# Pure_Digit.net
KiCad netlist of a schematic drawn in EAGLE
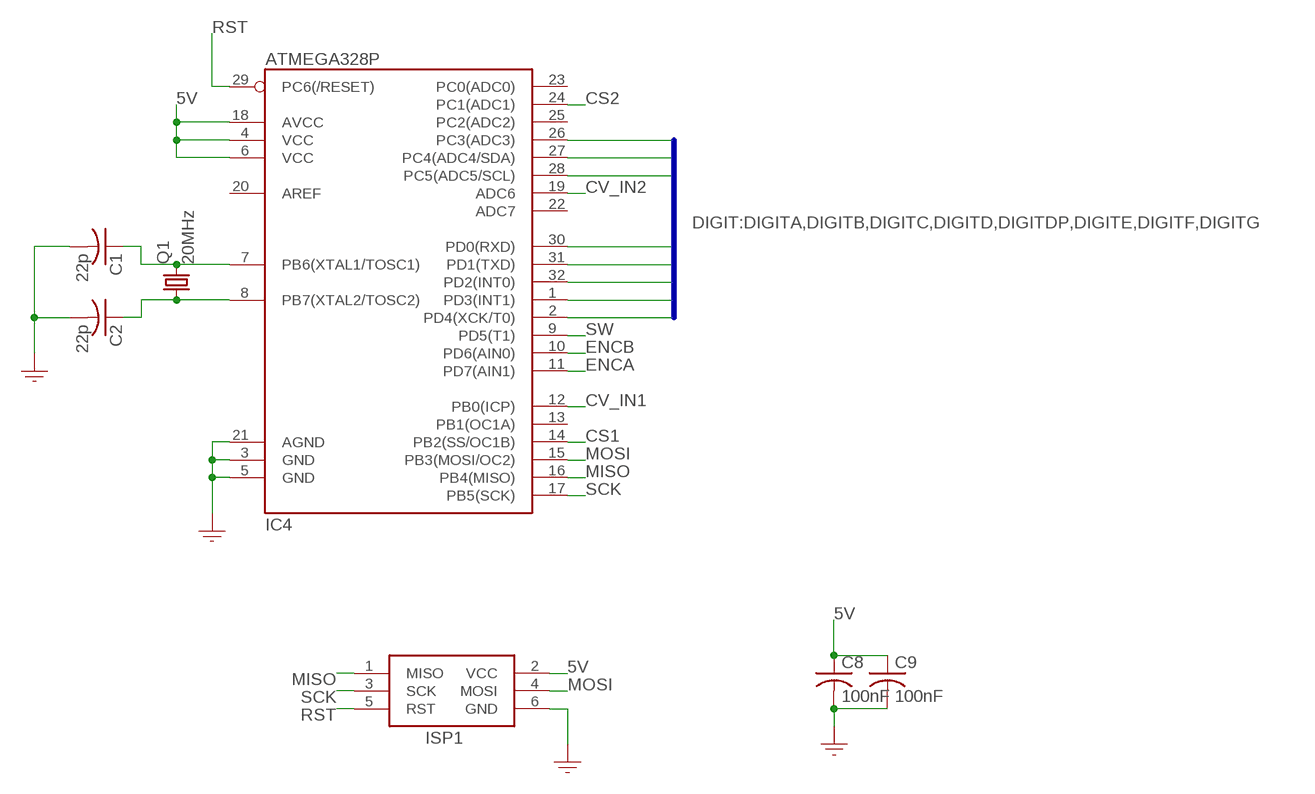
[diagram p0: schematic, sheet 1]
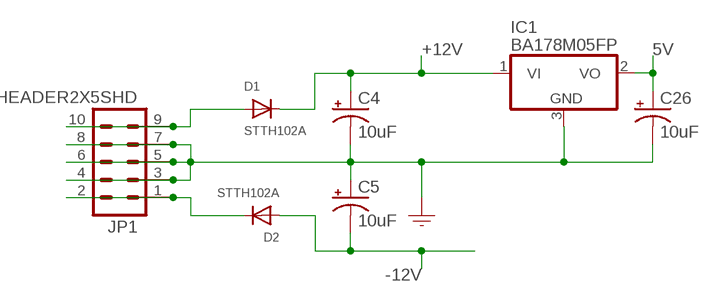
[diagram p1: schematic, sheet 2]
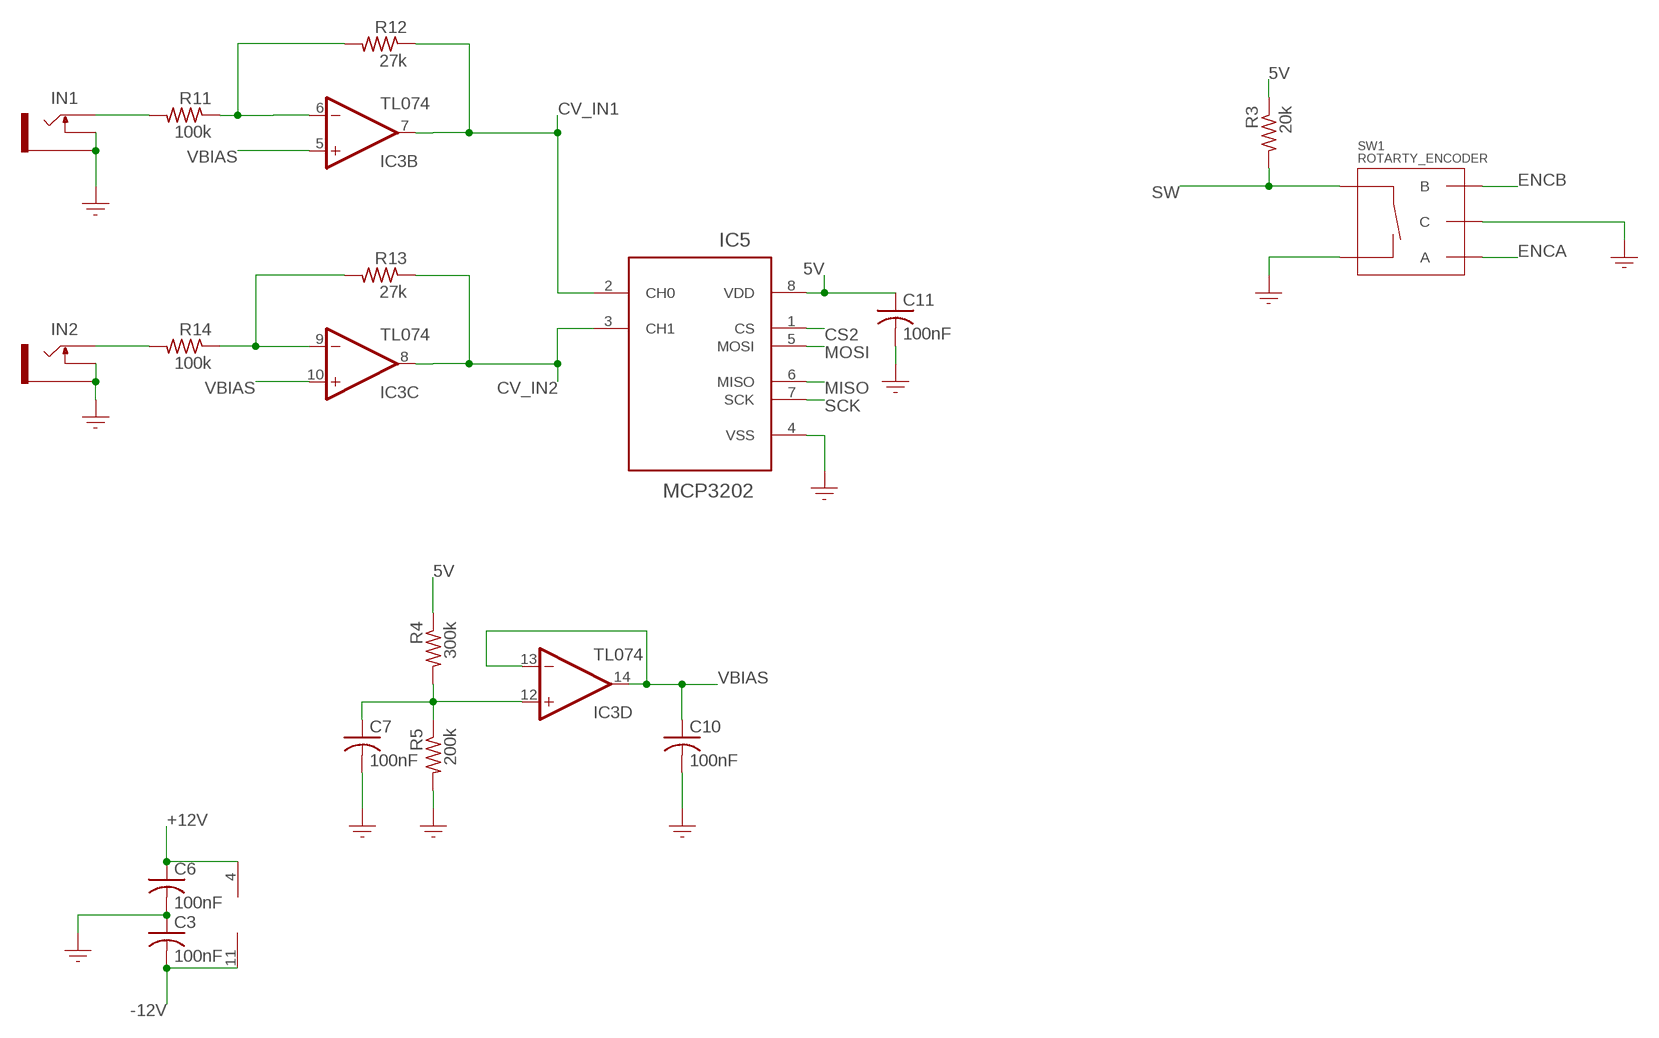
[diagram p2: schematic, sheet 3]
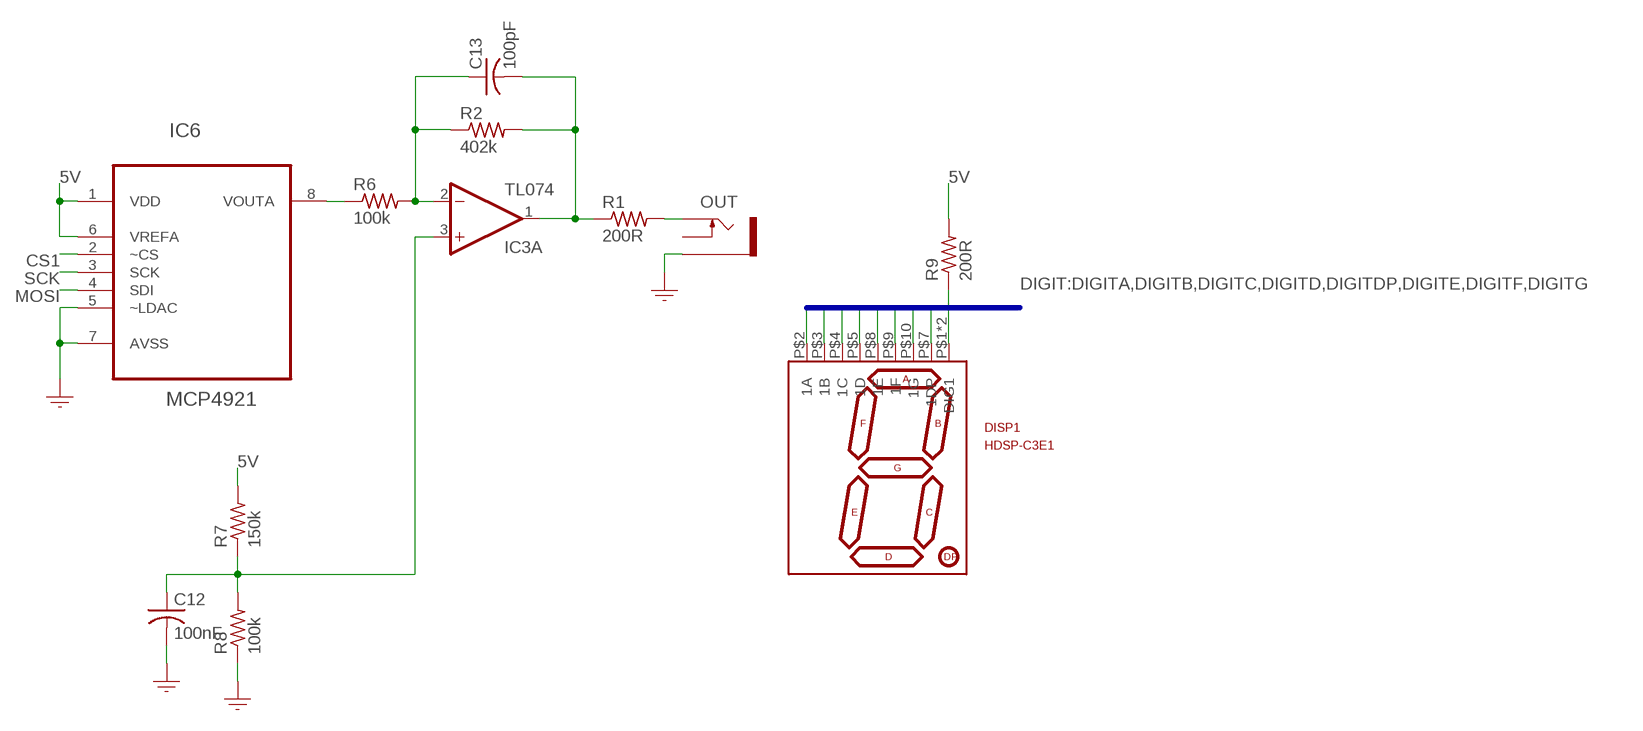
[diagram p3: schematic, sheet 4]

(export (version "E")
  (design (tool "Eeschema 10.0.6"))
  (components
    (comp (ref "C3")
      (value "100nF")
      (footprint "eagle-import:C0805")
      (libsource (lib "eagle-import") (part "CAPACITOR-USC0805"))
    )
    (comp (ref "C6")
      (value "100nF")
      (footprint "eagle-import:C0805")
      (libsource (lib "eagle-import") (part "CAPACITOR-USC0805"))
    )
    (comp (ref "C7")
      (value "100nF")
      (footprint "eagle-import:C0805")
      (libsource (lib "eagle-import") (part "CAPACITOR-USC0805"))
    )
    (comp (ref "C10")
      (value "100nF")
      (footprint "eagle-import:C0805")
      (libsource (lib "eagle-import") (part "CAPACITOR-USC0805"))
    )
    (comp (ref "C11")
      (value "100nF")
      (footprint "eagle-import:C0805")
      (libsource (lib "eagle-import") (part "CAPACITOR-USC0805"))
    )
    (comp (ref "IC3")
      (value "TL074")
      (footprint "eagle-import:SO14")
      (libsource (lib "eagle-import") (part "OPAMP_QUADD"))
    )
    (comp (ref "IC5")
      (value "MCP3202")
      (footprint "eagle-import:SOIC--8")
      (libsource (lib "eagle-import") (part "ADC_DUAL_12B_MCP3202"))
    )
    (comp (ref "IN1")
      (value "PJ301M-12")
      (footprint "eagle-import:PJ301M-12")
      (libsource (lib "eagle-import") (part "SOCKET_MONO_3.5MMPJ301M-12"))
    )
    (comp (ref "IN2")
      (value "PJ301M-12")
      (footprint "eagle-import:PJ301M-12")
      (libsource (lib "eagle-import") (part "SOCKET_MONO_3.5MMPJ301M-12"))
    )
    (comp (ref "R3")
      (value "20k")
      (footprint "eagle-import:R0805")
      (libsource (lib "eagle-import") (part "RESISTOR_USR0805"))
    )
    (comp (ref "R4")
      (value "300k")
      (footprint "eagle-import:R0805")
      (libsource (lib "eagle-import") (part "RESISTOR_USR0805"))
    )
    (comp (ref "R5")
      (value "200k")
      (footprint "eagle-import:R0805")
      (libsource (lib "eagle-import") (part "RESISTOR_USR0805"))
    )
    (comp (ref "R11")
      (value "100k")
      (footprint "eagle-import:R0805")
      (libsource (lib "eagle-import") (part "RESISTOR_USR0805"))
    )
    (comp (ref "R12")
      (value "27k")
      (footprint "eagle-import:R0805")
      (libsource (lib "eagle-import") (part "RESISTOR_USR0805"))
    )
    (comp (ref "R13")
      (value "27k")
      (footprint "eagle-import:R0805")
      (libsource (lib "eagle-import") (part "RESISTOR_USR0805"))
    )
    (comp (ref "R14")
      (value "100k")
      (footprint "eagle-import:R0805")
      (libsource (lib "eagle-import") (part "RESISTOR_USR0805"))
    )
    (comp (ref "SW1")
      (value "ROTARTY_ENCODER")
      (footprint "eagle-import:ROTARY_ENC_PLAIN")
      (libsource (lib "eagle-import") (part "ROTARTY_ENCODER"))
    )
    (comp (ref "C1")
      (value "22p")
      (footprint "eagle-import:C0805")
      (libsource (lib "eagle-import") (part "CAPACITOR-USC0805"))
    )
    (comp (ref "C2")
      (value "22p")
      (footprint "eagle-import:C0805")
      (libsource (lib "eagle-import") (part "CAPACITOR-USC0805"))
    )
    (comp (ref "C8")
      (value "100nF")
      (footprint "eagle-import:C0805")
      (libsource (lib "eagle-import") (part "CAPACITOR-USC0805"))
    )
    (comp (ref "C9")
      (value "100nF")
      (footprint "eagle-import:C0805")
      (libsource (lib "eagle-import") (part "CAPACITOR-USC0805"))
    )
    (comp (ref "IC4")
      (value "ATMEGA328P")
      (footprint "eagle-import:TQFP32-08")
      (libsource (lib "eagle-import") (part "MICROPROCESSOR_ATMEGA328_SMT"))
    )
    (comp (ref "ISP1")
      (value "HEADER2X3-6")
      (footprint "eagle-import:AVRISP")
      (libsource (lib "eagle-import") (part "HEADER2X3-6"))
    )
    (comp (ref "Q1")
      (value "20MHz")
      (footprint "eagle-import:SM49")
      (libsource (lib "eagle-import") (part "CRYSTALSM49"))
    )
    (comp (ref "C12")
      (value "100nF")
      (footprint "eagle-import:C0805")
      (libsource (lib "eagle-import") (part "CAPACITOR-USC0805"))
    )
    (comp (ref "C13")
      (value "100pF")
      (footprint "eagle-import:C0805")
      (libsource (lib "eagle-import") (part "CAPACITOR-USC0805"))
    )
    (comp (ref "DISP1")
      (value "HDSP-C3E1")
      (footprint "eagle-import:7-SEGMENT-1DIGIT")
      (libsource (lib "eagle-import") (part "DISPLAY_7-SEGMENT-1DIGIT"))
    )
    (comp (ref "IC6")
      (value "MCP4921")
      (footprint "eagle-import:SOIC8")
      (libsource (lib "eagle-import") (part "DAC_SINGLE_12B_MCP4921"))
    )
    (comp (ref "OUT")
      (value "PJ301M-12")
      (footprint "eagle-import:PJ301M-12")
      (libsource (lib "eagle-import") (part "SOCKET_MONO_3.5MMPJ301M-12"))
    )
    (comp (ref "R1")
      (value "200R")
      (footprint "eagle-import:R0805")
      (libsource (lib "eagle-import") (part "RESISTOR_USR0805"))
    )
    (comp (ref "R2")
      (value "402k")
      (footprint "eagle-import:R0805")
      (libsource (lib "eagle-import") (part "RESISTOR_USR0805"))
    )
    (comp (ref "R6")
      (value "100k")
      (footprint "eagle-import:R0805")
      (libsource (lib "eagle-import") (part "RESISTOR_USR0805"))
    )
    (comp (ref "R7")
      (value "150k")
      (footprint "eagle-import:R0805")
      (libsource (lib "eagle-import") (part "RESISTOR_USR0805"))
    )
    (comp (ref "R8")
      (value "100k")
      (footprint "eagle-import:R0805")
      (libsource (lib "eagle-import") (part "RESISTOR_USR0805"))
    )
    (comp (ref "R9")
      (value "200R")
      (footprint "eagle-import:R0805")
      (libsource (lib "eagle-import") (part "RESISTOR_USR0805"))
    )
    (comp (ref "C4")
      (value "10uF")
      (footprint "eagle-import:153CLV-0505")
      (libsource (lib "eagle-import") (part "CAPACITOR_POL-US153CLV-0505"))
    )
    (comp (ref "C5")
      (value "10uF")
      (footprint "eagle-import:153CLV-0505")
      (libsource (lib "eagle-import") (part "CAPACITOR_POL-US153CLV-0505"))
    )
    (comp (ref "C26")
      (value "10uF")
      (footprint "eagle-import:153CLV-0505")
      (libsource (lib "eagle-import") (part "CAPACITOR_POL-US153CLV-0505"))
    )
    (comp (ref "D1")
      (value "STTH102A")
      (footprint "eagle-import:SMADIODE")
      (libsource (lib "eagle-import") (part "DIODESMA"))
    )
    (comp (ref "D2")
      (value "STTH102A")
      (footprint "eagle-import:SMADIODE")
      (libsource (lib "eagle-import") (part "DIODESMA"))
    )
    (comp (ref "IC1")
      (value "BA178M05FP")
      (footprint "eagle-import:TO252")
      (libsource (lib "eagle-import") (part "VOLTAGE_REG_POSDT05"))
    )
    (comp (ref "JP1")
      (value "HEADER2X5SHD")
      (footprint "eagle-import:2X5-SHROUDED")
      (libsource (lib "eagle-import") (part "HEADER2X5SHD"))
    )
  )
  (nets
    (net (code "3") (name "+12V") (class "Default")
      (node (ref "C4") (pin "+") (pinfunction "+_+") (pintype "passive"))
      (node (ref "C6") (pin "1") (pinfunction "1_1") (pintype "passive"))
      (node (ref "D1") (pin "C") (pinfunction "C_C") (pintype "passive"))
      (node (ref "IC1") (pin "1") (pinfunction "VI_1") (pintype "input"))
      (node (ref "IC3") (pin "4") (pinfunction "V+_4") (pintype "power_in"))
    )
    (net (code "4") (name "-12V") (class "Default")
      (node (ref "C3") (pin "2") (pinfunction "2_2") (pintype "passive"))
      (node (ref "C5") (pin "-") (pinfunction "-_-") (pintype "passive"))
      (node (ref "D2") (pin "A") (pinfunction "A_A") (pintype "passive"))
      (node (ref "IC3") (pin "11") (pinfunction "V-_11") (pintype "power_in"))
    )
    (net (code "7") (name "5V") (class "Default")
      (node (ref "C11") (pin "1") (pinfunction "1_1") (pintype "passive"))
      (node (ref "C26") (pin "+") (pinfunction "+_+") (pintype "passive"))
      (node (ref "C8") (pin "1") (pinfunction "1_1") (pintype "passive"))
      (node (ref "C9") (pin "1") (pinfunction "1_1") (pintype "passive"))
      (node (ref "IC1") (pin "2") (pinfunction "VO_2") (pintype "passive"))
      (node (ref "IC4") (pin "18") (pinfunction "AVCC_18") (pintype "bidirectional"))
      (node (ref "IC4") (pin "4") (pinfunction "VCC_4") (pintype "bidirectional"))
      (node (ref "IC4") (pin "6") (pinfunction "VCC_6") (pintype "bidirectional"))
      (node (ref "IC5") (pin "8") (pinfunction "VDD_8") (pintype "bidirectional"))
      (node (ref "IC6") (pin "1") (pinfunction "VDD_1") (pintype "power_in"))
      (node (ref "IC6") (pin "6") (pinfunction "VREFA_6") (pintype "input"))
      (node (ref "ISP1") (pin "2") (pinfunction "VCC_2") (pintype "power_in"))
      (node (ref "R3") (pin "1") (pinfunction "1_1") (pintype "passive"))
      (node (ref "R4") (pin "1") (pinfunction "1_1") (pintype "passive"))
      (node (ref "R7") (pin "2") (pinfunction "2_2") (pintype "passive"))
      (node (ref "R9") (pin "2") (pinfunction "2_2") (pintype "passive"))
    )
    (net (code "8") (name "CS1") (class "Default")
      (node (ref "IC4") (pin "14") (pinfunction "PB2(SS/OC1B)_14") (pintype "bidirectional"))
      (node (ref "IC6") (pin "2") (pinfunction "~{CS}_2") (pintype "input"))
    )
    (net (code "9") (name "CS2") (class "Default")
      (node (ref "IC4") (pin "24") (pinfunction "PC1(ADC1)_24") (pintype "bidirectional"))
      (node (ref "IC5") (pin "1") (pinfunction "CS_1") (pintype "bidirectional"))
    )
    (net (code "10") (name "CV_IN1") (class "Default")
      (node (ref "IC3") (pin "7") (pinfunction "OUT_7") (pintype "output"))
      (node (ref "IC4") (pin "12") (pinfunction "PB0(ICP)_12") (pintype "bidirectional"))
      (node (ref "IC5") (pin "2") (pinfunction "CH0_2") (pintype "bidirectional"))
      (node (ref "R12") (pin "1") (pinfunction "1_1") (pintype "passive"))
    )
    (net (code "11") (name "CV_IN2") (class "Default")
      (node (ref "IC3") (pin "8") (pinfunction "OUT_8") (pintype "output"))
      (node (ref "IC4") (pin "19") (pinfunction "ADC6_19") (pintype "bidirectional"))
      (node (ref "IC5") (pin "3") (pinfunction "CH1_3") (pintype "bidirectional"))
      (node (ref "R13") (pin "1") (pinfunction "1_1") (pintype "passive"))
    )
    (net (code "12") (name "DIGITA") (class "Default")
      (node (ref "DISP1") (pin "P$2") (pinfunction "1A_P$2") (pintype "bidirectional"))
      (node (ref "IC4") (pin "30") (pinfunction "PD0(RXD)_30") (pintype "bidirectional"))
    )
    (net (code "13") (name "DIGITB") (class "Default")
      (node (ref "DISP1") (pin "P$3") (pinfunction "1B_P$3") (pintype "bidirectional"))
      (node (ref "IC4") (pin "28") (pinfunction "PC5(ADC5/SCL)_28") (pintype "bidirectional"))
    )
    (net (code "14") (name "DIGITC") (class "Default")
      (node (ref "DISP1") (pin "P$4") (pinfunction "1C_P$4") (pintype "bidirectional"))
      (node (ref "IC4") (pin "27") (pinfunction "PC4(ADC4/SDA)_27") (pintype "bidirectional"))
    )
    (net (code "15") (name "DIGITD") (class "Default")
      (node (ref "DISP1") (pin "P$5") (pinfunction "1D_P$5") (pintype "bidirectional"))
      (node (ref "IC4") (pin "26") (pinfunction "PC3(ADC3)_26") (pintype "bidirectional"))
    )
    (net (code "16") (name "DIGITDP") (class "Default")
      (node (ref "DISP1") (pin "P$7") (pinfunction "1DP_P$7") (pintype "bidirectional"))
      (node (ref "IC4") (pin "1") (pinfunction "PD3(INT1)_1") (pintype "bidirectional"))
    )
    (net (code "17") (name "DIGITE") (class "Default")
      (node (ref "DISP1") (pin "P$8") (pinfunction "1E_P$8") (pintype "bidirectional"))
      (node (ref "IC4") (pin "2") (pinfunction "PD4(XCK/T0)_2") (pintype "bidirectional"))
    )
    (net (code "18") (name "DIGITF") (class "Default")
      (node (ref "DISP1") (pin "P$9") (pinfunction "1F_P$9") (pintype "bidirectional"))
      (node (ref "IC4") (pin "32") (pinfunction "PD2(INT0)_32") (pintype "bidirectional"))
    )
    (net (code "19") (name "DIGITG") (class "Default")
      (node (ref "DISP1") (pin "P$10") (pinfunction "1G_P$10") (pintype "bidirectional"))
      (node (ref "IC4") (pin "31") (pinfunction "PD1(TXD)_31") (pintype "bidirectional"))
    )
    (net (code "20") (name "ENCA") (class "Default")
      (node (ref "IC4") (pin "11") (pinfunction "PD7(AIN1)_11") (pintype "bidirectional"))
      (node (ref "SW1") (pin "A") (pinfunction "A_A") (pintype "bidirectional"))
    )
    (net (code "21") (name "ENCB") (class "Default")
      (node (ref "IC4") (pin "10") (pinfunction "PD6(AIN0)_10") (pintype "bidirectional"))
      (node (ref "SW1") (pin "B") (pinfunction "B_B") (pintype "bidirectional"))
    )
    (net (code "22") (name "GND") (class "Default")
      (node (ref "C1") (pin "2") (pinfunction "2_2") (pintype "passive"))
      (node (ref "C10") (pin "2") (pinfunction "2_2") (pintype "passive"))
      (node (ref "C11") (pin "2") (pinfunction "2_2") (pintype "passive"))
      (node (ref "C12") (pin "2") (pinfunction "2_2") (pintype "passive"))
      (node (ref "C2") (pin "2") (pinfunction "2_2") (pintype "passive"))
      (node (ref "C26") (pin "-") (pinfunction "-_-") (pintype "passive"))
      (node (ref "C3") (pin "1") (pinfunction "1_1") (pintype "passive"))
      (node (ref "C4") (pin "-") (pinfunction "-_-") (pintype "passive"))
      (node (ref "C5") (pin "+") (pinfunction "+_+") (pintype "passive"))
      (node (ref "C6") (pin "2") (pinfunction "2_2") (pintype "passive"))
      (node (ref "C7") (pin "2") (pinfunction "2_2") (pintype "passive"))
      (node (ref "C8") (pin "2") (pinfunction "2_2") (pintype "passive"))
      (node (ref "C9") (pin "2") (pinfunction "2_2") (pintype "passive"))
      (node (ref "IC1") (pin "3") (pinfunction "GND_3") (pintype "passive"))
      (node (ref "IC4") (pin "21") (pinfunction "AGND_21") (pintype "bidirectional"))
      (node (ref "IC4") (pin "3") (pinfunction "GND_3") (pintype "bidirectional"))
      (node (ref "IC4") (pin "5") (pinfunction "GND_5") (pintype "bidirectional"))
      (node (ref "IC5") (pin "4") (pinfunction "VSS_4") (pintype "bidirectional"))
      (node (ref "IC6") (pin "5") (pinfunction "~{LDAC}_5") (pintype "input"))
      (node (ref "IC6") (pin "7") (pinfunction "AVSS_7") (pintype "passive"))
      (node (ref "IN1") (pin "GND") (pinfunction "SLEEVE_GND") (pintype "passive"))
      (node (ref "IN1") (pin "NORM") (pinfunction "SWITCH_NORM") (pintype "passive"))
      (node (ref "IN2") (pin "GND") (pinfunction "SLEEVE_GND") (pintype "passive"))
      (node (ref "IN2") (pin "NORM") (pinfunction "SWITCH_NORM") (pintype "passive"))
      (node (ref "ISP1") (pin "6") (pinfunction "GND_6") (pintype "power_in"))
      (node (ref "JP1") (pin "3") (pinfunction "3_3") (pintype "passive"))
      (node (ref "JP1") (pin "4") (pinfunction "4_4") (pintype "passive"))
      (node (ref "JP1") (pin "5") (pinfunction "5_5") (pintype "passive"))
      (node (ref "JP1") (pin "6") (pinfunction "6_6") (pintype "passive"))
      (node (ref "JP1") (pin "7") (pinfunction "7_7") (pintype "passive"))
      (node (ref "JP1") (pin "8") (pinfunction "8_8") (pintype "passive"))
      (node (ref "OUT") (pin "GND") (pinfunction "SLEEVE_GND") (pintype "passive"))
      (node (ref "R5") (pin "2") (pinfunction "2_2") (pintype "passive"))
      (node (ref "R8") (pin "1") (pinfunction "1_1") (pintype "passive"))
      (node (ref "SW1") (pin "C") (pinfunction "C_C") (pintype "bidirectional"))
      (node (ref "SW1") (pin "SW-") (pinfunction "SW-_SW-") (pintype "bidirectional"))
    )
    (net (code "23") (name "MISO") (class "Default")
      (node (ref "IC4") (pin "16") (pinfunction "PB4(MISO)_16") (pintype "bidirectional"))
      (node (ref "IC5") (pin "6") (pinfunction "MISO_6") (pintype "bidirectional"))
      (node (ref "ISP1") (pin "1") (pinfunction "MISO_1") (pintype "input"))
    )
    (net (code "24") (name "MOSI") (class "Default")
      (node (ref "IC4") (pin "15") (pinfunction "PB3(MOSI/OC2)_15") (pintype "bidirectional"))
      (node (ref "IC5") (pin "5") (pinfunction "MOSI_5") (pintype "bidirectional"))
      (node (ref "IC6") (pin "4") (pinfunction "SDI_4") (pintype "input"))
      (node (ref "ISP1") (pin "4") (pinfunction "MOSI_4") (pintype "output"))
    )
    (net (code "25") (name "Net-(D1-PadA)") (class "Default")
      (node (ref "D1") (pin "A") (pinfunction "A_A") (pintype "passive"))
      (node (ref "JP1") (pin "10") (pinfunction "10_10") (pintype "passive"))
      (node (ref "JP1") (pin "9") (pinfunction "9_9") (pintype "passive"))
    )
    (net (code "26") (name "Net-(D2-PadC)") (class "Default")
      (node (ref "D2") (pin "C") (pinfunction "C_C") (pintype "passive"))
      (node (ref "JP1") (pin "1") (pinfunction "1_1") (pintype "passive"))
      (node (ref "JP1") (pin "2") (pinfunction "2_2") (pintype "passive"))
    )
    (net (code "27") (name "Net-(DISP1-DIG1-PadP$1)") (class "Default")
      (node (ref "DISP1") (pin "P$1") (pinfunction "DIG1_P$1") (pintype "bidirectional"))
      (node (ref "DISP1") (pin "P$6") (pinfunction "DIG1_P$6") (pintype "bidirectional"))
      (node (ref "R9") (pin "1") (pinfunction "1_1") (pintype "passive"))
    )
    (net (code "28") (name "Net-(IC3A-+IN)") (class "Default")
      (node (ref "C12") (pin "1") (pinfunction "1_1") (pintype "passive"))
      (node (ref "IC3") (pin "3") (pinfunction "+IN_3") (pintype "input"))
      (node (ref "R7") (pin "1") (pinfunction "1_1") (pintype "passive"))
      (node (ref "R8") (pin "2") (pinfunction "2_2") (pintype "passive"))
    )
    (net (code "29") (name "Net-(IC3A--IN)") (class "Default")
      (node (ref "C13") (pin "1") (pinfunction "1_1") (pintype "passive"))
      (node (ref "IC3") (pin "2") (pinfunction "-IN_2") (pintype "input"))
      (node (ref "R2") (pin "1") (pinfunction "1_1") (pintype "passive"))
      (node (ref "R6") (pin "2") (pinfunction "2_2") (pintype "passive"))
    )
    (net (code "30") (name "Net-(IC3A-OUT)") (class "Default")
      (node (ref "C13") (pin "2") (pinfunction "2_2") (pintype "passive"))
      (node (ref "IC3") (pin "1") (pinfunction "OUT_1") (pintype "output"))
      (node (ref "R1") (pin "1") (pinfunction "1_1") (pintype "passive"))
      (node (ref "R2") (pin "2") (pinfunction "2_2") (pintype "passive"))
    )
    (net (code "31") (name "Net-(IC3B--IN)") (class "Default")
      (node (ref "IC3") (pin "6") (pinfunction "-IN_6") (pintype "input"))
      (node (ref "R11") (pin "1") (pinfunction "1_1") (pintype "passive"))
      (node (ref "R12") (pin "2") (pinfunction "2_2") (pintype "passive"))
    )
    (net (code "32") (name "Net-(IC3C--IN)") (class "Default")
      (node (ref "IC3") (pin "9") (pinfunction "-IN_9") (pintype "input"))
      (node (ref "R13") (pin "2") (pinfunction "2_2") (pintype "passive"))
      (node (ref "R14") (pin "1") (pinfunction "1_1") (pintype "passive"))
    )
    (net (code "33") (name "Net-(IC3D-+IN)") (class "Default")
      (node (ref "C7") (pin "1") (pinfunction "1_1") (pintype "passive"))
      (node (ref "IC3") (pin "12") (pinfunction "+IN_12") (pintype "input"))
      (node (ref "R4") (pin "2") (pinfunction "2_2") (pintype "passive"))
      (node (ref "R5") (pin "1") (pinfunction "1_1") (pintype "passive"))
    )
    (net (code "34") (name "Net-(IC4-PB6(XTAL1{slash}TOSC1))") (class "Default")
      (node (ref "C1") (pin "1") (pinfunction "1_1") (pintype "passive"))
      (node (ref "IC4") (pin "7") (pinfunction "PB6(XTAL1/TOSC1)_7") (pintype "bidirectional"))
      (node (ref "Q1") (pin "2") (pinfunction "2_2") (pintype "passive"))
    )
    (net (code "35") (name "Net-(IC4-PB7(XTAL2{slash}TOSC2))") (class "Default")
      (node (ref "C2") (pin "1") (pinfunction "1_1") (pintype "passive"))
      (node (ref "IC4") (pin "8") (pinfunction "PB7(XTAL2/TOSC2)_8") (pintype "bidirectional"))
      (node (ref "Q1") (pin "1") (pinfunction "1_1") (pintype "passive"))
    )
    (net (code "36") (name "Net-(IC6-VOUTA)") (class "Default")
      (node (ref "IC6") (pin "8") (pinfunction "VOUTA_8") (pintype "output"))
      (node (ref "R6") (pin "1") (pinfunction "1_1") (pintype "passive"))
    )
    (net (code "37") (name "Net-(IN1-PadTIP)") (class "Default")
      (node (ref "IN1") (pin "TIP") (pinfunction "TIP_TIP") (pintype "passive"))
      (node (ref "R11") (pin "2") (pinfunction "2_2") (pintype "passive"))
    )
    (net (code "38") (name "Net-(IN2-PadTIP)") (class "Default")
      (node (ref "IN2") (pin "TIP") (pinfunction "TIP_TIP") (pintype "passive"))
      (node (ref "R14") (pin "2") (pinfunction "2_2") (pintype "passive"))
    )
    (net (code "39") (name "Net-(OUT-PadTIP)") (class "Default")
      (node (ref "OUT") (pin "TIP") (pinfunction "TIP_TIP") (pintype "passive"))
      (node (ref "R1") (pin "2") (pinfunction "2_2") (pintype "passive"))
    )
    (net (code "40") (name "RST") (class "Default")
      (node (ref "IC4") (pin "29") (pinfunction "PC6(/RESET)_29") (pintype "bidirectional"))
      (node (ref "ISP1") (pin "5") (pinfunction "RST_5") (pintype "output"))
    )
    (net (code "41") (name "SCK") (class "Default")
      (node (ref "IC4") (pin "17") (pinfunction "PB5(SCK)_17") (pintype "bidirectional"))
      (node (ref "IC5") (pin "7") (pinfunction "SCK_7") (pintype "bidirectional"))
      (node (ref "IC6") (pin "3") (pinfunction "SCK_3") (pintype "input"))
      (node (ref "ISP1") (pin "3") (pinfunction "SCK_3") (pintype "output"))
    )
    (net (code "42") (name "SW") (class "Default")
      (node (ref "IC4") (pin "9") (pinfunction "PD5(T1)_9") (pintype "bidirectional"))
      (node (ref "R3") (pin "2") (pinfunction "2_2") (pintype "passive"))
      (node (ref "SW1") (pin "SW+") (pinfunction "SW+_SW+") (pintype "bidirectional"))
    )
    (net (code "43") (name "VBIAS") (class "Default")
      (node (ref "C10") (pin "1") (pinfunction "1_1") (pintype "passive"))
      (node (ref "IC3") (pin "10") (pinfunction "+IN_10") (pintype "input"))
      (node (ref "IC3") (pin "13") (pinfunction "-IN_13") (pintype "input"))
      (node (ref "IC3") (pin "14") (pinfunction "OUT_14") (pintype "output"))
      (node (ref "IC3") (pin "5") (pinfunction "+IN_5") (pintype "input"))
    )
    (net (code "44") (name "unconnected-(IC4-ADC7-Pad22)") (class "Default")
      (node (ref "IC4") (pin "22") (pinfunction "ADC7_22") (pintype "bidirectional"))
    )
    (net (code "45") (name "unconnected-(IC4-AREF-Pad20)") (class "Default")
      (node (ref "IC4") (pin "20") (pinfunction "AREF_20") (pintype "bidirectional"))
    )
    (net (code "46") (name "unconnected-(IC4-PB1(OC1A)-Pad13)") (class "Default")
      (node (ref "IC4") (pin "13") (pinfunction "PB1(OC1A)_13") (pintype "bidirectional"))
    )
    (net (code "47") (name "unconnected-(IC4-PC0(ADC0)-Pad23)") (class "Default")
      (node (ref "IC4") (pin "23") (pinfunction "PC0(ADC0)_23") (pintype "bidirectional"))
    )
    (net (code "48") (name "unconnected-(IC4-PC2(ADC2)-Pad25)") (class "Default")
      (node (ref "IC4") (pin "25") (pinfunction "PC2(ADC2)_25") (pintype "bidirectional"))
    )
    (net (code "49") (name "unconnected-(OUT-SWITCH-PadNORM)") (class "Default")
      (node (ref "OUT") (pin "NORM") (pinfunction "SWITCH_NORM") (pintype "passive"))
    )
  )
)
